# zeta2rework_lw_v32_rework.net
KiCad netlist of a schematic drawn in EAGLE
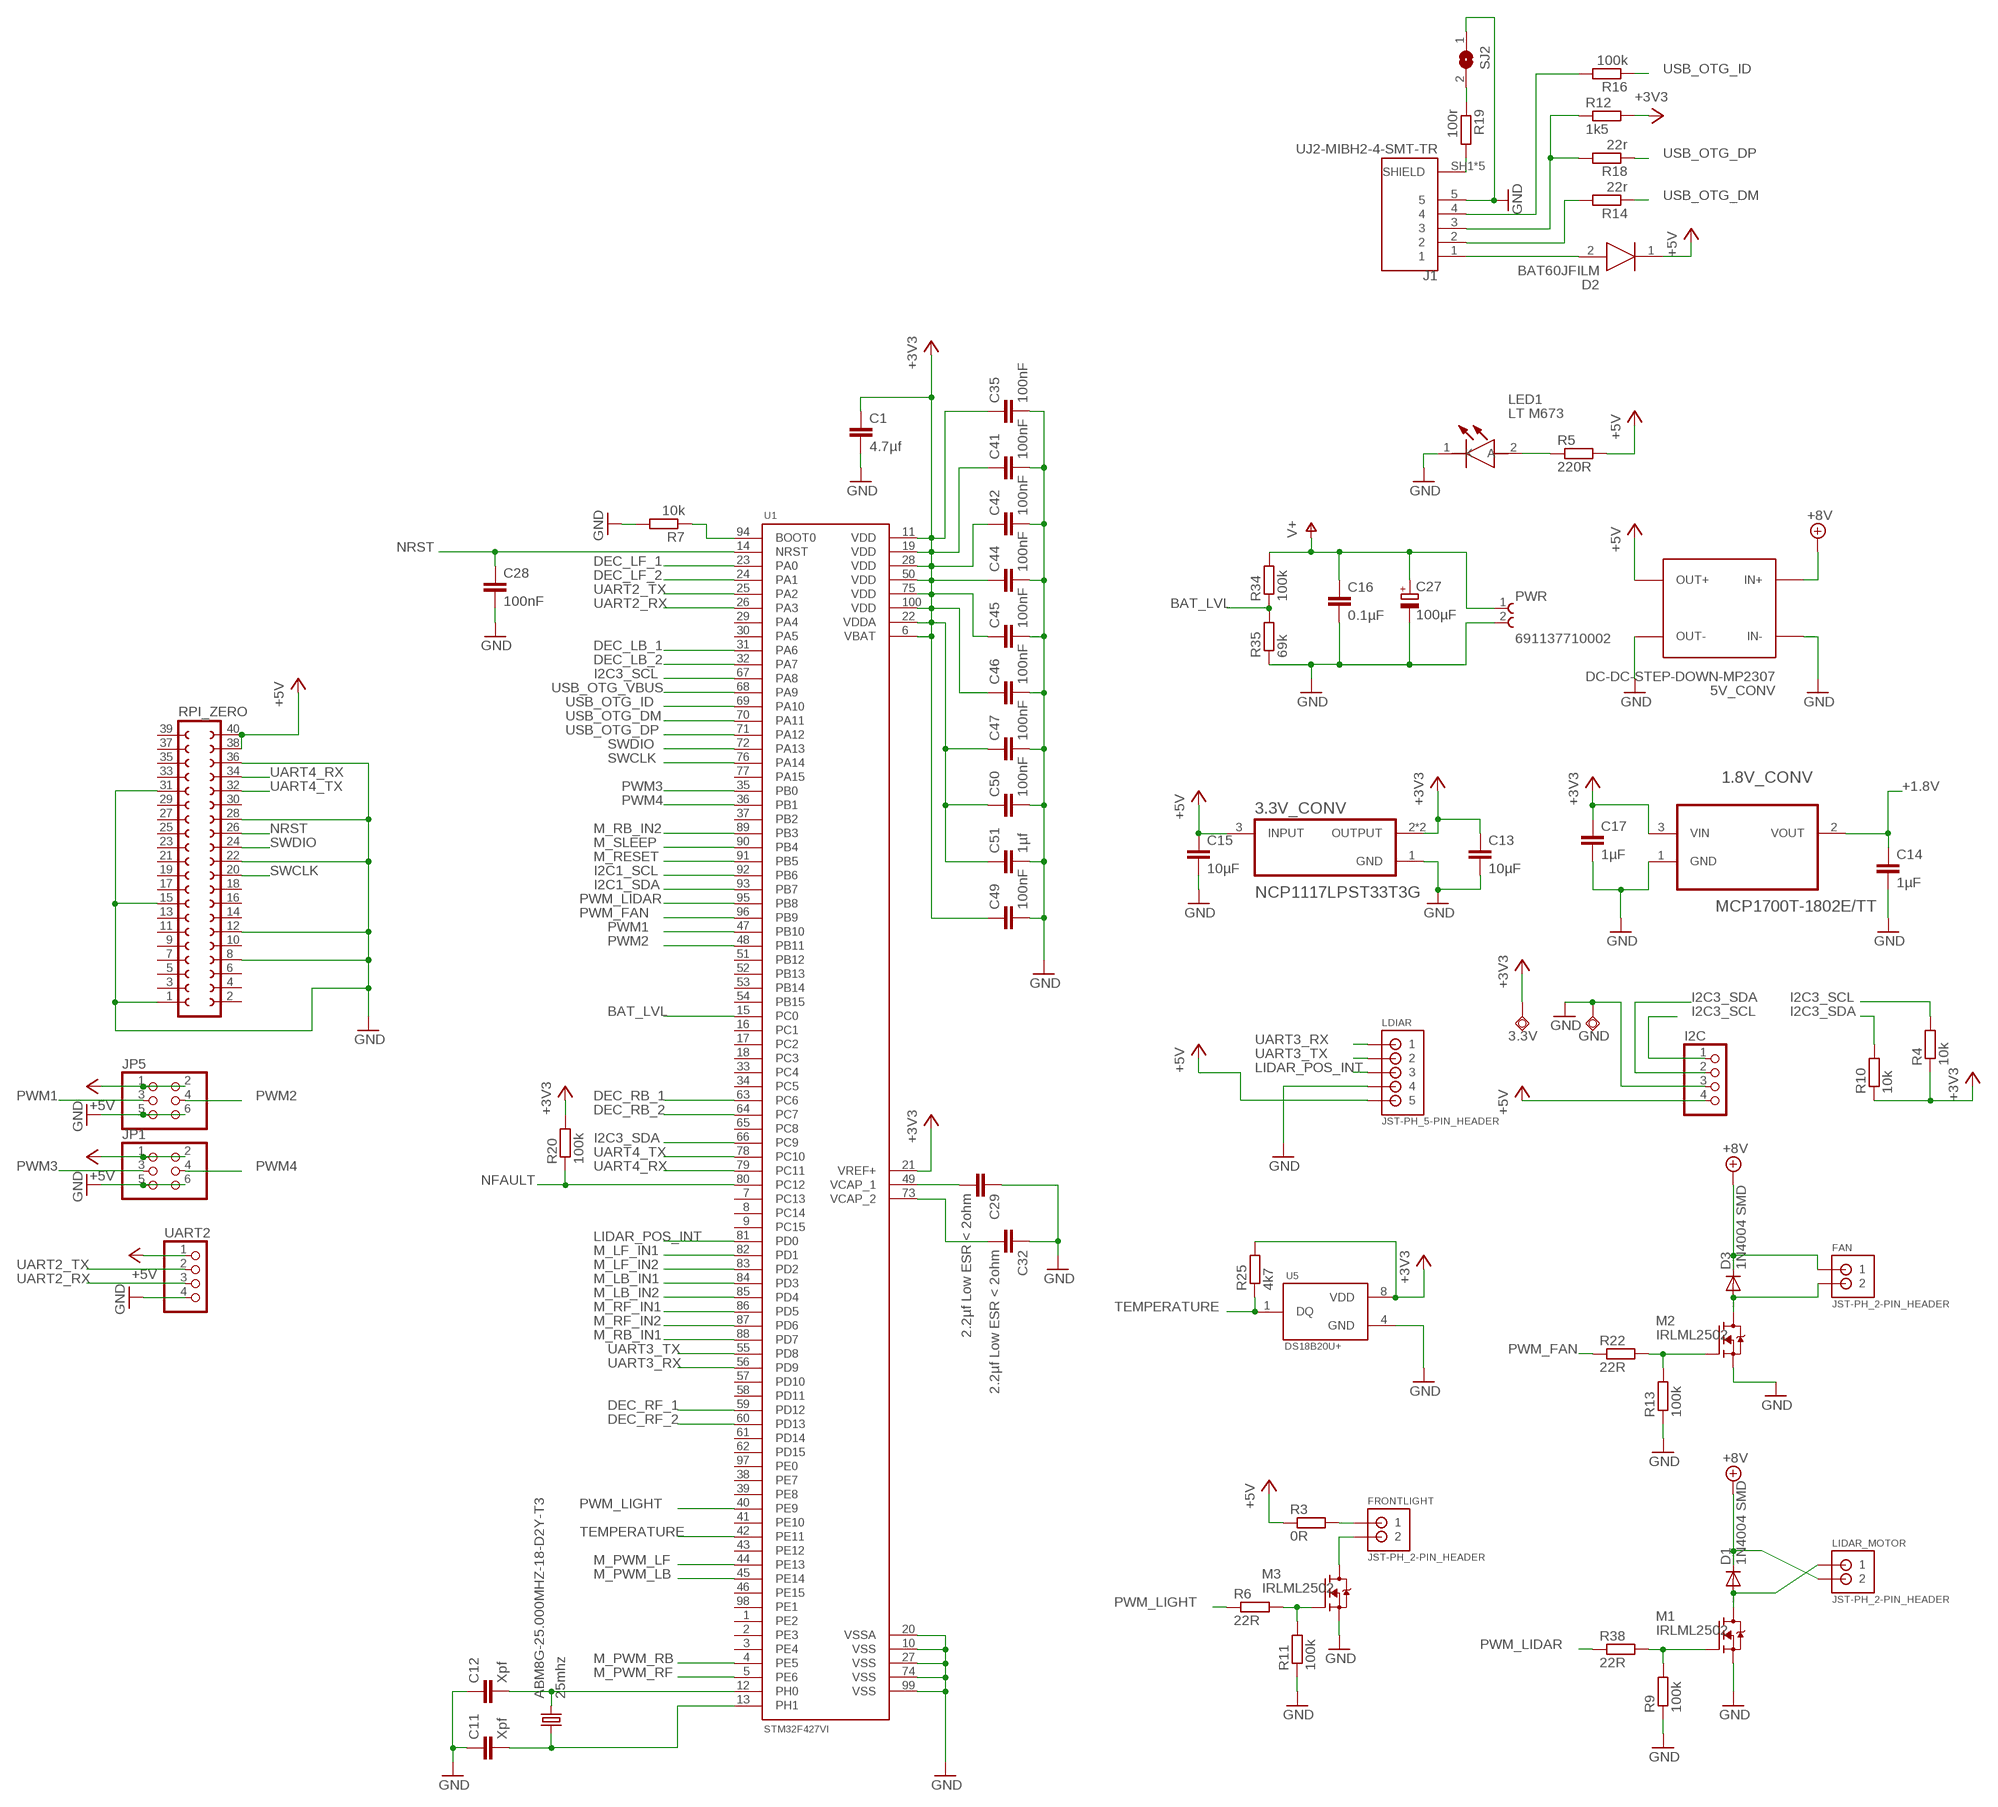
[diagram p0: schematic, sheet 1, part 1 of 2]
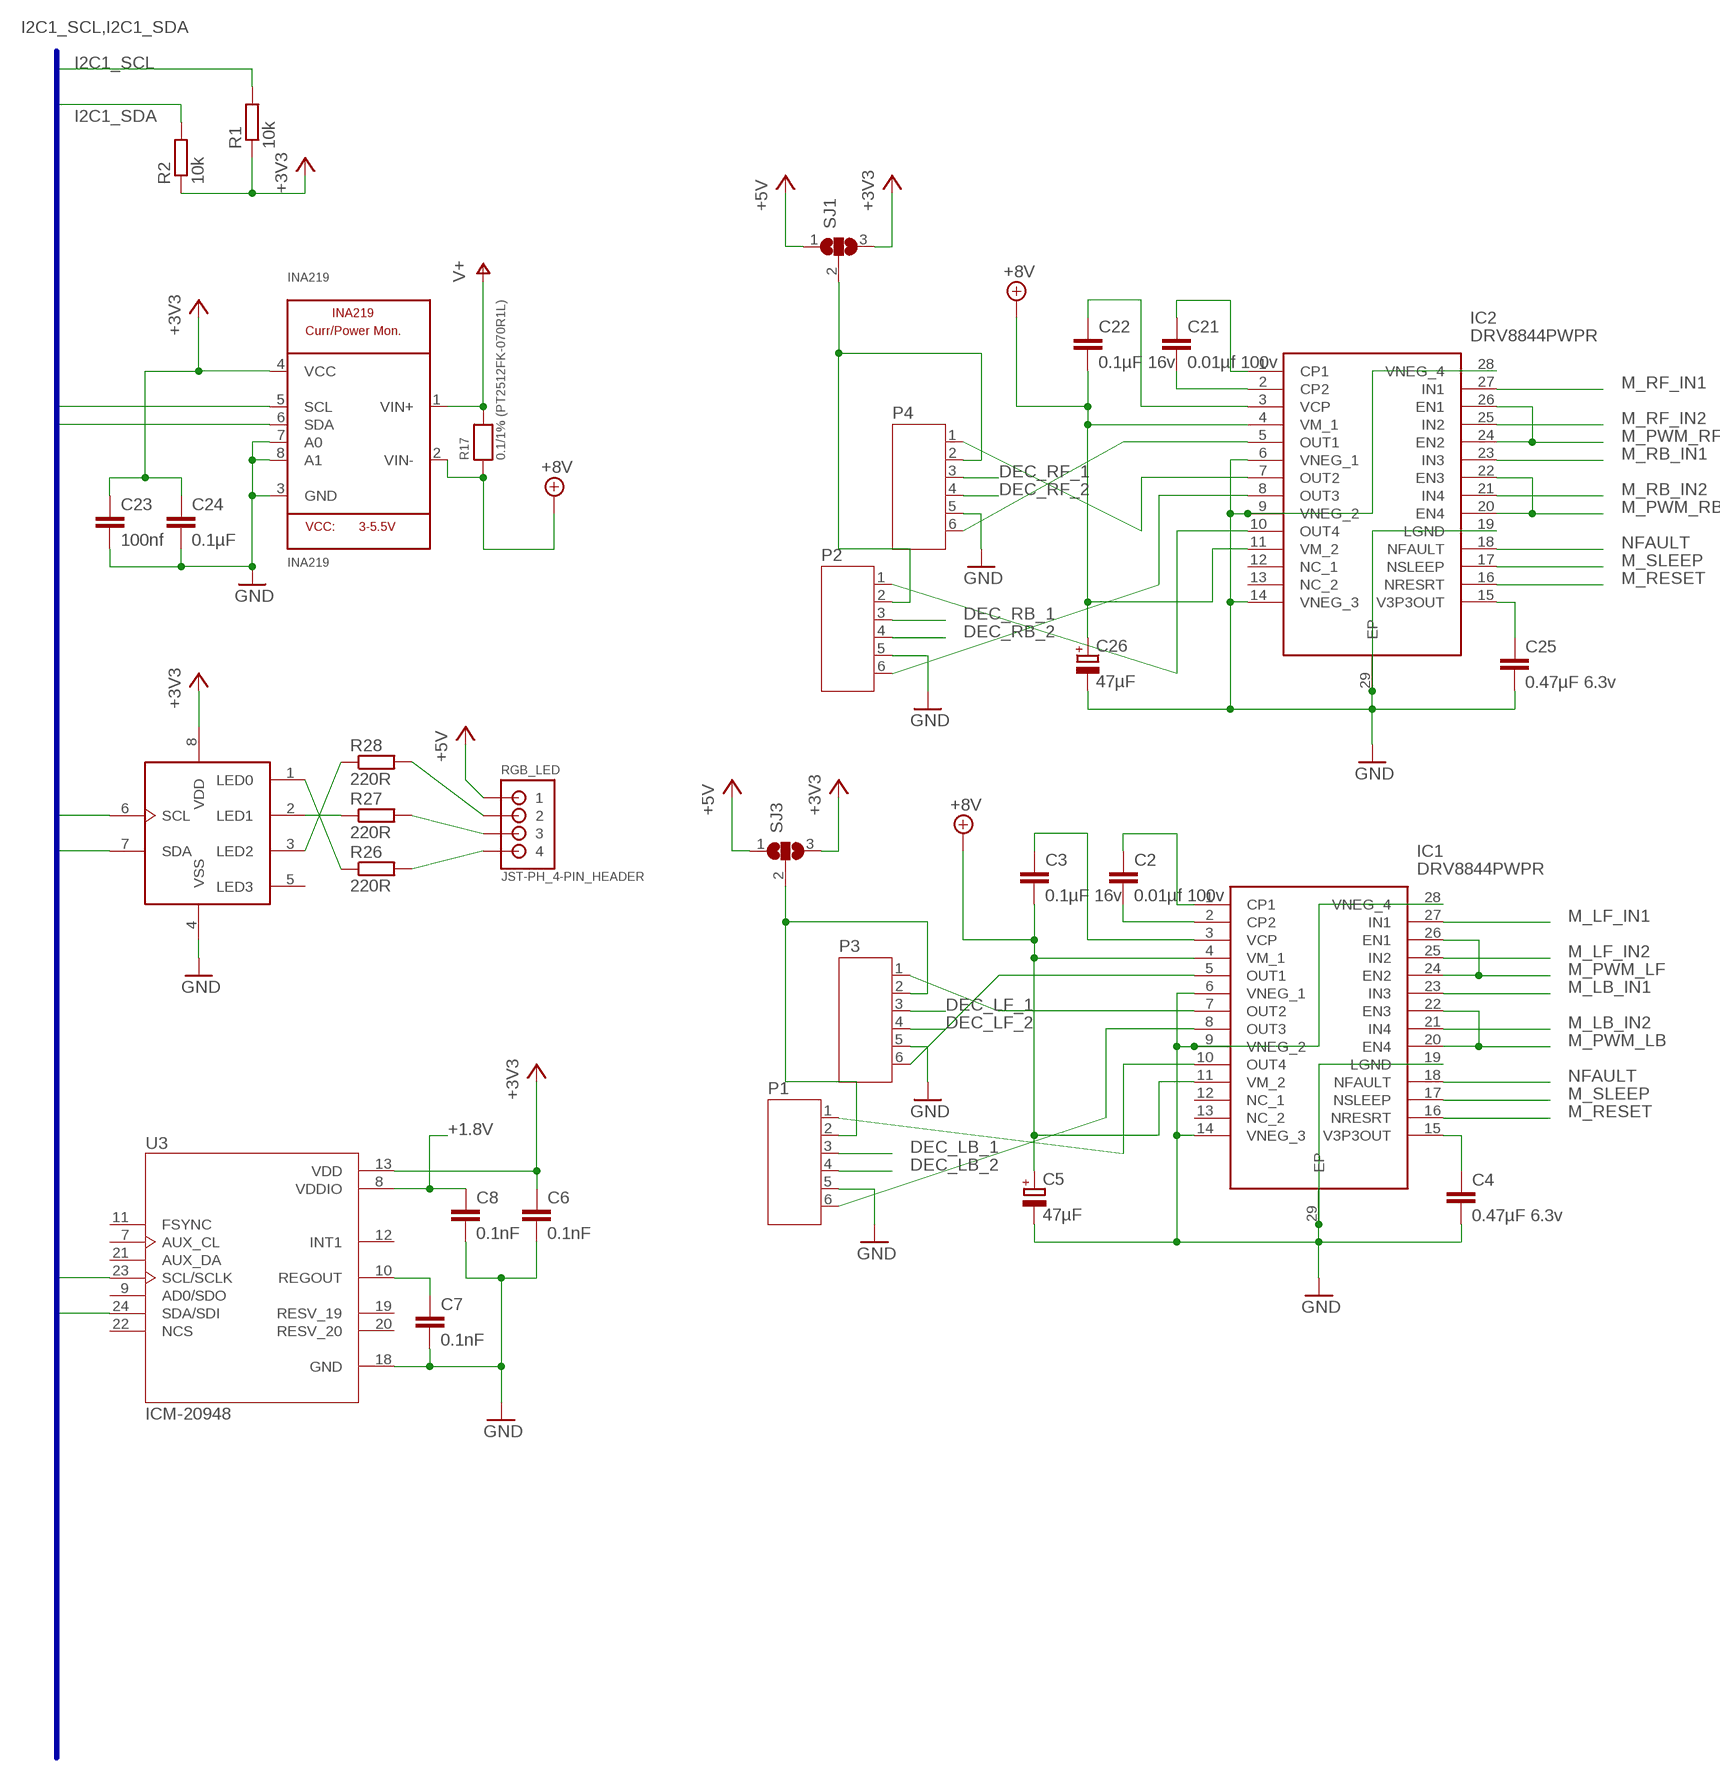
[diagram p1: schematic, sheet 1, part 2 of 2]

(export (version "E")
  (design (tool "Eeschema 10.0.6"))
  (components
    (comp (ref "1.8V_CONV")
      (value "MCP1700T-1802E/TT")
      (footprint "eagle-import:SOT95P237X112-3N")
      (fields (field (name "MF") "Microchip") (field (name "MP") "MCP1700T-2102E/TT"))
      (libsource (lib "eagle-import") (part "MCP1700T-2102E/TT"))
    )
    (comp (ref "3.3V")
      (value "TPSQTP20R")
      (footprint "eagle-import:TP20R")
      (libsource (lib "eagle-import") (part "TPSQTP20R"))
    )
    (comp (ref "3.3V_CONV")
      (value "NCP1117LPST33T3G")
      (footprint "eagle-import:SOT230P700X175-4N")
      (fields (field (name "MF") "ON Semiconductor"))
      (libsource (lib "eagle-import") (part "NCP1117LPST33T3G"))
    )
    (comp (ref "5V_CONV")
      (value "DC-DC-STEP-DOWN-MP2307")
      (footprint "eagle-import:DC-DC-STEP-DOWN-MP2307")
      (libsource (lib "eagle-import") (part "DC-DC-STEP-DOWN-MP2307"))
    )
    (comp (ref "ABM8G-25.000MHZ-18-D2Y-T3")
      (value "25mhz")
      (footprint "eagle-import:5.0X3.2_KX-9A")
      (libsource (lib "eagle-import") (part "KX-9A"))
    )
    (comp (ref "C1")
      (value "4.7µf")
      (footprint "eagle-import:C0603")
      (libsource (lib "eagle-import") (part "C-EUC0603"))
    )
    (comp (ref "C2")
      (value "0.01µf 100v")
      (footprint "eagle-import:C0603")
      (libsource (lib "eagle-import") (part "C-EUC0603"))
    )
    (comp (ref "C3")
      (value "0.1µF 16v")
      (footprint "eagle-import:C0603")
      (libsource (lib "eagle-import") (part "C-EUC0603"))
    )
    (comp (ref "C4")
      (value "0.47µF 6.3v")
      (footprint "eagle-import:C0603")
      (libsource (lib "eagle-import") (part "C-EUC0603"))
    )
    (comp (ref "C5")
      (value "47µF")
      (footprint "eagle-import:UD-5X5,8_NICHICON")
      (libsource (lib "eagle-import") (part "CPOL-EUUD-5X5,8"))
    )
    (comp (ref "C6")
      (value "0.1nF")
      (footprint "eagle-import:C0603")
      (libsource (lib "eagle-import") (part "C-EUC0603"))
    )
    (comp (ref "C7")
      (value "0.1nF")
      (footprint "eagle-import:C0603")
      (libsource (lib "eagle-import") (part "C-EUC0603"))
    )
    (comp (ref "C8")
      (value "0.1nF")
      (footprint "eagle-import:C0603")
      (libsource (lib "eagle-import") (part "C-EUC0603"))
    )
    (comp (ref "C11")
      (value "Xpf")
      (footprint "eagle-import:C0603")
      (libsource (lib "eagle-import") (part "C-EUC0603"))
    )
    (comp (ref "C12")
      (value "Xpf")
      (footprint "eagle-import:C0603")
      (libsource (lib "eagle-import") (part "C-EUC0603"))
    )
    (comp (ref "C13")
      (value "10µF")
      (footprint "eagle-import:C1206")
      (libsource (lib "eagle-import") (part "C-EUC1206"))
    )
    (comp (ref "C14")
      (value "1µF")
      (footprint "eagle-import:C0603")
      (libsource (lib "eagle-import") (part "C-EUC0603"))
    )
    (comp (ref "C15")
      (value "10µF")
      (footprint "eagle-import:C1206")
      (libsource (lib "eagle-import") (part "C-EUC1206"))
    )
    (comp (ref "C16")
      (value "0.1µF")
      (footprint "eagle-import:C0603")
      (libsource (lib "eagle-import") (part "C-EUC0603"))
    )
    (comp (ref "C17")
      (value "1µF")
      (footprint "eagle-import:C0603")
      (libsource (lib "eagle-import") (part "C-EUC0603"))
    )
    (comp (ref "C21")
      (value "0.01µf 100v")
      (footprint "eagle-import:C0603")
      (libsource (lib "eagle-import") (part "C-EUC0603"))
    )
    (comp (ref "C22")
      (value "0.1µF 16v")
      (footprint "eagle-import:C0603")
      (libsource (lib "eagle-import") (part "C-EUC0603"))
    )
    (comp (ref "C23")
      (value "100nf")
      (footprint "eagle-import:C0603")
      (libsource (lib "eagle-import") (part "C-EUC0603"))
    )
    (comp (ref "C24")
      (value "0.1µF")
      (footprint "eagle-import:C0603")
      (libsource (lib "eagle-import") (part "C-EUC0603"))
    )
    (comp (ref "C25")
      (value "0.47µF 6.3v")
      (footprint "eagle-import:C0603")
      (libsource (lib "eagle-import") (part "C-EUC0603"))
    )
    (comp (ref "C26")
      (value "47µF")
      (footprint "eagle-import:UD-5X5,8_NICHICON")
      (libsource (lib "eagle-import") (part "CPOL-EUUD-5X5,8"))
    )
    (comp (ref "C27")
      (value "100µF")
      (footprint "eagle-import:UD-5X5,8_NICHICON")
      (libsource (lib "eagle-import") (part "CPOL-EUUD-5X5,8"))
    )
    (comp (ref "C28")
      (value "100nF")
      (footprint "eagle-import:C0603")
      (libsource (lib "eagle-import") (part "C-EUC0603"))
    )
    (comp (ref "C29")
      (value "2.2µf Low ESR < 2ohm")
      (footprint "eagle-import:C1206")
      (libsource (lib "eagle-import") (part "C-EUC1206"))
    )
    (comp (ref "C32")
      (value "2.2µf Low ESR < 2ohm")
      (footprint "eagle-import:C1206")
      (libsource (lib "eagle-import") (part "C-EUC1206"))
    )
    (comp (ref "C35")
      (value "100nF")
      (footprint "eagle-import:C0603")
      (libsource (lib "eagle-import") (part "C-EUC0603"))
    )
    (comp (ref "C41")
      (value "100nF")
      (footprint "eagle-import:C0603")
      (libsource (lib "eagle-import") (part "C-EUC0603"))
    )
    (comp (ref "C42")
      (value "100nF")
      (footprint "eagle-import:C0603")
      (libsource (lib "eagle-import") (part "C-EUC0603"))
    )
    (comp (ref "C44")
      (value "100nF")
      (footprint "eagle-import:C0603")
      (libsource (lib "eagle-import") (part "C-EUC0603"))
    )
    (comp (ref "C45")
      (value "100nF")
      (footprint "eagle-import:C0603")
      (libsource (lib "eagle-import") (part "C-EUC0603"))
    )
    (comp (ref "C46")
      (value "100nF")
      (footprint "eagle-import:C0603")
      (libsource (lib "eagle-import") (part "C-EUC0603"))
    )
    (comp (ref "C47")
      (value "100nF")
      (footprint "eagle-import:C0603")
      (libsource (lib "eagle-import") (part "C-EUC0603"))
    )
    (comp (ref "C49")
      (value "100nF")
      (footprint "eagle-import:C0603")
      (libsource (lib "eagle-import") (part "C-EUC0603"))
    )
    (comp (ref "C50")
      (value "100nF")
      (footprint "eagle-import:C0603")
      (libsource (lib "eagle-import") (part "C-EUC0603"))
    )
    (comp (ref "C51")
      (value "1µf")
      (footprint "eagle-import:C0603")
      (libsource (lib "eagle-import") (part "C-EUC0603"))
    )
    (comp (ref "D1")
      (value "1N4004 SMD")
      (footprint "eagle-import:DO214AC")
      (libsource (lib "eagle-import") (part "DIODE-DO214AC"))
    )
    (comp (ref "D2")
      (value "BAT60JFILM")
      (footprint "eagle-import:SOD2513X117N")
      (fields (field (name "MOUSER_PART_NUMBER") "511-BAT60JFILM") (field (name "RS_PART_NUMBER") "1458781"))
      (libsource (lib "eagle-import") (part "BAT60JFILM"))
    )
    (comp (ref "D3")
      (value "1N4004 SMD")
      (footprint "eagle-import:DO214AC")
      (libsource (lib "eagle-import") (part "DIODE-DO214AC"))
    )
    (comp (ref "FAN")
      (value "JST-PH_2-PIN_HEADER")
      (footprint "eagle-import:JST_B2B-PH_HEADER")
      (libsource (lib "eagle-import") (part "JST-PH_2-PIN_HEADER"))
    )
    (comp (ref "FRONTLIGHT")
      (value "JST-PH_2-PIN_HEADER")
      (footprint "eagle-import:JST_B2B-PH_HEADER")
      (libsource (lib "eagle-import") (part "JST-PH_2-PIN_HEADER"))
    )
    (comp (ref "GND")
      (value "TPSQTP20R")
      (footprint "eagle-import:TP20R")
      (libsource (lib "eagle-import") (part "TPSQTP20R"))
    )
    (comp (ref "I2C")
      (value "PINHD-1X4")
      (footprint "eagle-import:1X04")
      (libsource (lib "eagle-import") (part "PINHD-1X4"))
    )
    (comp (ref "IC1")
      (value "DRV8844PWPR")
      (footprint "eagle-import:SOP65P640X120-29N")
      (fields (field (name "MOUSER_PART_NUMBER") "595-DRV8844PWPR"))
      (libsource (lib "eagle-import") (part "DRV8844PWPR"))
    )
    (comp (ref "IC2")
      (value "DRV8844PWPR")
      (footprint "eagle-import:SOP65P640X120-29N")
      (fields (field (name "MOUSER_PART_NUMBER") "595-DRV8844PWPR"))
      (libsource (lib "eagle-import") (part "DRV8844PWPR"))
    )
    (comp (ref "INA219")
      (value "INA219")
      (footprint "eagle-import:SOT23-8")
      (fields (field (name "MF") "Texas Instruments"))
      (libsource (lib "eagle-import") (part "INA219"))
    )
    (comp (ref "J1")
      (value "UJ2-MIBH2-4-SMT-TR")
      (footprint "eagle-import:CUI_UJ2-MIBH2-4-SMT-TR")
      (fields (field (name "MF") "CUI Inc."))
      (libsource (lib "eagle-import") (part "UJ2-MIBH2-4-SMT-TR"))
    )
    (comp (ref "JP1")
      (value "PINHD-2X3")
      (footprint "eagle-import:2X03")
      (libsource (lib "eagle-import") (part "PINHD-2X3"))
    )
    (comp (ref "JP5")
      (value "PINHD-2X3")
      (footprint "eagle-import:2X03")
      (libsource (lib "eagle-import") (part "PINHD-2X3"))
    )
    (comp (ref "LDIAR")
      (value "JST-PH_5-PIN_HEADER")
      (footprint "eagle-import:JST_B5B-PH_HEADER")
      (libsource (lib "eagle-import") (part "JST-PH_5-PIN_HEADER"))
    )
    (comp (ref "LED1")
      (value "LT M673")
      (footprint "eagle-import:LTM673-N1R2-25")
      (fields
        (field (name "MANUFACTURER_PART_NUMBER") "LT M673-N1R2-25")
        (field (name "MOUSER_PART_NUMBER") "720-LTM673N1R225Z")
        (field (name "RS_PART_NUMBER") "9133231")
      )
      (libsource (lib "eagle-import") (part "LT_M673-N1R2-25"))
    )
    (comp (ref "LIDAR_MOTOR")
      (value "JST-PH_2-PIN_HEADER")
      (footprint "eagle-import:JST_B2B-PH_HEADER")
      (libsource (lib "eagle-import") (part "JST-PH_2-PIN_HEADER"))
    )
    (comp (ref "M1")
      (value "IRLML2502")
      (footprint "eagle-import:SOT23")
      (fields (field (name "MF") "Infineon") (field (name "MP") "IRLML2502TRPBF"))
      (libsource (lib "eagle-import") (part "IRLML2502TRPBF"))
    )
    (comp (ref "M2")
      (value "IRLML2502")
      (footprint "eagle-import:SOT23")
      (fields (field (name "MF") "Infineon") (field (name "MP") "IRLML2502TRPBF"))
      (libsource (lib "eagle-import") (part "IRLML2502TRPBF"))
    )
    (comp (ref "M3")
      (value "IRLML2502")
      (footprint "eagle-import:SOT23")
      (fields (field (name "MF") "Infineon") (field (name "MP") "IRLML2502TRPBF"))
      (libsource (lib "eagle-import") (part "IRLML2502TRPBF"))
    )
    (comp (ref "P1")
      (value "JST-PH6")
      (footprint "eagle-import:JST-PH6")
      (libsource (lib "eagle-import") (part "JST-PH6"))
    )
    (comp (ref "P2")
      (value "JST-PH6")
      (footprint "eagle-import:JST-PH6")
      (libsource (lib "eagle-import") (part "JST-PH6"))
    )
    (comp (ref "P3")
      (value "JST-PH6")
      (footprint "eagle-import:JST-PH6")
      (libsource (lib "eagle-import") (part "JST-PH6"))
    )
    (comp (ref "P4")
      (value "JST-PH6")
      (footprint "eagle-import:JST-PH6")
      (libsource (lib "eagle-import") (part "JST-PH6"))
    )
    (comp (ref "PCA9533")
      (value "PCA9533")
      (footprint "eagle-import:SOIC8")
      (libsource (lib "eagle-import") (part "PCA9533"))
    )
    (comp (ref "PWR")
      (value "691137710002")
      (footprint "eagle-import:691137710002")
      (fields (field (name "MF") "Wurth Electronics"))
      (libsource (lib "eagle-import") (part "691137710002"))
    )
    (comp (ref "R1")
      (value "10k")
      (footprint "eagle-import:R0603")
      (libsource (lib "eagle-import") (part "R-EU_R0603"))
    )
    (comp (ref "R2")
      (value "10k")
      (footprint "eagle-import:R0603")
      (libsource (lib "eagle-import") (part "R-EU_R0603"))
    )
    (comp (ref "R3")
      (value "0R")
      (footprint "eagle-import:R0603")
      (libsource (lib "eagle-import") (part "R-EU_R0603"))
    )
    (comp (ref "R4")
      (value "10k")
      (footprint "eagle-import:R0603")
      (libsource (lib "eagle-import") (part "R-EU_R0603"))
    )
    (comp (ref "R5")
      (value "220R")
      (footprint "eagle-import:R0603")
      (libsource (lib "eagle-import") (part "R-EU_R0603"))
    )
    (comp (ref "R6")
      (value "22R")
      (footprint "eagle-import:R0603")
      (libsource (lib "eagle-import") (part "R-EU_R0603"))
    )
    (comp (ref "R7")
      (value "10k")
      (footprint "eagle-import:R0603")
      (libsource (lib "eagle-import") (part "R-EU_R0603"))
    )
    (comp (ref "R9")
      (value "100k")
      (footprint "eagle-import:R0603")
      (libsource (lib "eagle-import") (part "R-EU_R0603"))
    )
    (comp (ref "R10")
      (value "10k")
      (footprint "eagle-import:R0603")
      (libsource (lib "eagle-import") (part "R-EU_R0603"))
    )
    (comp (ref "R11")
      (value "100k")
      (footprint "eagle-import:R0603")
      (libsource (lib "eagle-import") (part "R-EU_R0603"))
    )
    (comp (ref "R12")
      (value "1k5")
      (footprint "eagle-import:R0603")
      (libsource (lib "eagle-import") (part "R-EU_R0603"))
    )
    (comp (ref "R13")
      (value "100k")
      (footprint "eagle-import:R0603")
      (libsource (lib "eagle-import") (part "R-EU_R0603"))
    )
    (comp (ref "R14")
      (value "22r")
      (footprint "eagle-import:R0603")
      (libsource (lib "eagle-import") (part "R-EU_R0603"))
    )
    (comp (ref "R16")
      (value "100k")
      (footprint "eagle-import:R0603")
      (libsource (lib "eagle-import") (part "R-EU_R0603"))
    )
    (comp (ref "R17")
      (value "0.1/1% (PT2512FK-070R1L)")
      (footprint "eagle-import:2512")
      (libsource (lib "eagle-import") (part "RESISTOR2512"))
    )
    (comp (ref "R18")
      (value "22r")
      (footprint "eagle-import:R0603")
      (libsource (lib "eagle-import") (part "R-EU_R0603"))
    )
    (comp (ref "R19")
      (value "100r")
      (footprint "eagle-import:R0603")
      (libsource (lib "eagle-import") (part "R-EU_R0603"))
    )
    (comp (ref "R20")
      (value "100k")
      (footprint "eagle-import:R0603")
      (libsource (lib "eagle-import") (part "R-EU_R0603"))
    )
    (comp (ref "R22")
      (value "22R")
      (footprint "eagle-import:R0603")
      (libsource (lib "eagle-import") (part "R-EU_R0603"))
    )
    (comp (ref "R25")
      (value "4k7")
      (footprint "eagle-import:R0603")
      (libsource (lib "eagle-import") (part "R-EU_R0603"))
    )
    (comp (ref "R26")
      (value "220R")
      (footprint "eagle-import:R0603")
      (libsource (lib "eagle-import") (part "R-EU_R0603"))
    )
    (comp (ref "R27")
      (value "220R")
      (footprint "eagle-import:R0603")
      (libsource (lib "eagle-import") (part "R-EU_R0603"))
    )
    (comp (ref "R28")
      (value "220R")
      (footprint "eagle-import:R0603")
      (libsource (lib "eagle-import") (part "R-EU_R0603"))
    )
    (comp (ref "R34")
      (value "100k")
      (footprint "eagle-import:R0603")
      (libsource (lib "eagle-import") (part "R-EU_R0603"))
    )
    (comp (ref "R35")
      (value "69k")
      (footprint "eagle-import:R0603")
      (libsource (lib "eagle-import") (part "R-EU_R0603"))
    )
    (comp (ref "R38")
      (value "22R")
      (footprint "eagle-import:R0603")
      (libsource (lib "eagle-import") (part "R-EU_R0603"))
    )
    (comp (ref "RGB_LED")
      (value "JST-PH_4-PIN_HEADER")
      (footprint "eagle-import:JST_B4B-PH_HEADER")
      (libsource (lib "eagle-import") (part "JST-PH_4-PIN_HEADER"))
    )
    (comp (ref "RPI_ZERO")
      (value "FE20-2")
      (footprint "eagle-import:FE20-2")
      (libsource (lib "eagle-import") (part "FE20-2"))
    )
    (comp (ref "SJ1")
      (value "SJ2W")
      (footprint "eagle-import:SJ_2")
      (libsource (lib "eagle-import") (part "SJ2W"))
    )
    (comp (ref "SJ2") (value "SJ") (footprint "eagle-import:SJ") (libsource (lib "eagle-import") (part "SJ")))
    (comp (ref "SJ3")
      (value "SJ2W")
      (footprint "eagle-import:SJ_2")
      (libsource (lib "eagle-import") (part "SJ2W"))
    )
    (comp (ref "U1")
      (value "STM32F427VI")
      (footprint "eagle-import:QFP50P1600X1600X160-100N")
      (fields (field (name "MF") "STMicroelectronics") (field (name "MP") "STM32F427VGT7"))
      (libsource (lib "eagle-import") (part "STM32F427VGT7"))
    )
    (comp (ref "U3")
      (value "ICM-20948")
      (footprint "eagle-import:QFN40P300X300X105-25N")
      (fields (field (name "MF") "TDK InvenSense"))
      (libsource (lib "eagle-import") (part "ICM-20948"))
    )
    (comp (ref "U5")
      (value "DS18B20U+")
      (footprint "eagle-import:SOP65P490X95-8N")
      (fields (field (name "MF") "Maxim"))
      (libsource (lib "eagle-import") (part "DS18B20U+"))
    )
    (comp (ref "UART2")
      (value "PINHD-1X4")
      (footprint "eagle-import:1X04")
      (libsource (lib "eagle-import") (part "PINHD-1X4"))
    )
  )
  (nets
    (net (code "1") (name "+3V3") (class "Default")
      (node (ref "1.8V_CONV") (pin "3") (pinfunction "VIN_3") (pintype "input"))
      (node (ref "3.3V") (pin "TP") (pinfunction "TP_TP") (pintype "input"))
      (node (ref "3.3V_CONV") (pin "2") (pinfunction "OUTPUT_2") (pintype "output"))
      (node (ref "3.3V_CONV") (pin "4") (pinfunction "OUTPUT_4") (pintype "output"))
      (node (ref "C1") (pin "1") (pinfunction "1_1") (pintype "passive"))
      (node (ref "C13") (pin "1") (pinfunction "1_1") (pintype "passive"))
      (node (ref "C17") (pin "1") (pinfunction "1_1") (pintype "passive"))
      (node (ref "C23") (pin "1") (pinfunction "1_1") (pintype "passive"))
      (node (ref "C24") (pin "1") (pinfunction "1_1") (pintype "passive"))
      (node (ref "C35") (pin "1") (pinfunction "1_1") (pintype "passive"))
      (node (ref "C41") (pin "1") (pinfunction "1_1") (pintype "passive"))
      (node (ref "C42") (pin "1") (pinfunction "1_1") (pintype "passive"))
      (node (ref "C44") (pin "1") (pinfunction "1_1") (pintype "passive"))
      (node (ref "C45") (pin "1") (pinfunction "1_1") (pintype "passive"))
      (node (ref "C46") (pin "1") (pinfunction "1_1") (pintype "passive"))
      (node (ref "C47") (pin "1") (pinfunction "1_1") (pintype "passive"))
      (node (ref "C49") (pin "1") (pinfunction "1_1") (pintype "passive"))
      (node (ref "C50") (pin "1") (pinfunction "1_1") (pintype "passive"))
      (node (ref "C51") (pin "1") (pinfunction "1_1") (pintype "passive"))
      (node (ref "C6") (pin "1") (pinfunction "1_1") (pintype "passive"))
      (node (ref "INA219") (pin "4") (pinfunction "VCC_4") (pintype "bidirectional"))
      (node (ref "PCA9533") (pin "8") (pinfunction "VDD_8") (pintype "power_in"))
      (node (ref "R1") (pin "1") (pinfunction "1_1") (pintype "passive"))
      (node (ref "R10") (pin "1") (pinfunction "1_1") (pintype "passive"))
      (node (ref "R12") (pin "2") (pinfunction "2_2") (pintype "passive"))
      (node (ref "R2") (pin "1") (pinfunction "1_1") (pintype "passive"))
      (node (ref "R20") (pin "2") (pinfunction "2_2") (pintype "passive"))
      (node (ref "R25") (pin "2") (pinfunction "2_2") (pintype "passive"))
      (node (ref "R4") (pin "1") (pinfunction "1_1") (pintype "passive"))
      (node (ref "SJ1") (pin "3") (pinfunction "3_3") (pintype "passive"))
      (node (ref "SJ3") (pin "3") (pinfunction "3_3") (pintype "passive"))
      (node (ref "U1") (pin "100") (pinfunction "VDD_100") (pintype "power_in"))
      (node (ref "U1") (pin "11") (pinfunction "VDD_11") (pintype "power_in"))
      (node (ref "U1") (pin "19") (pinfunction "VDD_19") (pintype "power_in"))
      (node (ref "U1") (pin "21") (pinfunction "VREF+_21") (pintype "power_in"))
      (node (ref "U1") (pin "22") (pinfunction "VDDA_22") (pintype "power_in"))
      (node (ref "U1") (pin "28") (pinfunction "VDD_28") (pintype "power_in"))
      (node (ref "U1") (pin "50") (pinfunction "VDD_50") (pintype "power_in"))
      (node (ref "U1") (pin "6") (pinfunction "VBAT_6") (pintype "power_in"))
      (node (ref "U1") (pin "75") (pinfunction "VDD_75") (pintype "power_in"))
      (node (ref "U3") (pin "13") (pinfunction "VDD_13") (pintype "power_in"))
      (node (ref "U5") (pin "8") (pinfunction "VDD_8") (pintype "power_in"))
    )
    (net (code "2") (name "+5V") (class "Default")
      (node (ref "3.3V_CONV") (pin "3") (pinfunction "INPUT_3") (pintype "input"))
      (node (ref "5V_CONV") (pin "OUT+") (pinfunction "OUT+_OUT+") (pintype "bidirectional"))
      (node (ref "C15") (pin "1") (pinfunction "1_1") (pintype "passive"))
      (node (ref "D2") (pin "1") (pinfunction "K_1") (pintype "bidirectional"))
      (node (ref "I2C") (pin "4") (pinfunction "4_4") (pintype "passive"))
      (node (ref "JP1") (pin "1") (pinfunction "1_1") (pintype "passive"))
      (node (ref "JP1") (pin "2") (pinfunction "2_2") (pintype "passive"))
      (node (ref "JP5") (pin "1") (pinfunction "1_1") (pintype "passive"))
      (node (ref "JP5") (pin "2") (pinfunction "2_2") (pintype "passive"))
      (node (ref "LDIAR") (pin "P5") (pinfunction "5_P5") (pintype "bidirectional"))
      (node (ref "R3") (pin "1") (pinfunction "1_1") (pintype "passive"))
      (node (ref "R5") (pin "2") (pinfunction "2_2") (pintype "passive"))
      (node (ref "RGB_LED") (pin "P1") (pinfunction "1_P1") (pintype "bidirectional"))
      (node (ref "RPI_ZERO") (pin "38") (pinfunction "38_38") (pintype "passive"))
      (node (ref "RPI_ZERO") (pin "40") (pinfunction "40_40") (pintype "passive"))
      (node (ref "SJ1") (pin "1") (pinfunction "1_1") (pintype "passive"))
      (node (ref "SJ3") (pin "1") (pinfunction "1_1") (pintype "passive"))
      (node (ref "UART2") (pin "1") (pinfunction "1_1") (pintype "passive"))
    )
    (net (code "3") (name "+8V") (class "Default")
      (node (ref "5V_CONV") (pin "IN+") (pinfunction "IN+_IN+") (pintype "bidirectional"))
      (node (ref "C22") (pin "2") (pinfunction "2_2") (pintype "passive"))
      (node (ref "C26") (pin "+") (pinfunction "+_+") (pintype "passive"))
      (node (ref "C3") (pin "2") (pinfunction "2_2") (pintype "passive"))
      (node (ref "C5") (pin "+") (pinfunction "+_+") (pintype "passive"))
      (node (ref "D1") (pin "C") (pinfunction "C_C") (pintype "passive"))
      (node (ref "D3") (pin "C") (pinfunction "C_C") (pintype "passive"))
      (node (ref "FAN") (pin "P1") (pinfunction "1_P1") (pintype "bidirectional"))
      (node (ref "IC1") (pin "11") (pinfunction "VM_2_11") (pintype "bidirectional"))
      (node (ref "IC1") (pin "4") (pinfunction "VM_1_4") (pintype "bidirectional"))
      (node (ref "IC2") (pin "11") (pinfunction "VM_2_11") (pintype "bidirectional"))
      (node (ref "IC2") (pin "4") (pinfunction "VM_1_4") (pintype "bidirectional"))
      (node (ref "INA219") (pin "2") (pinfunction "VIN-_2") (pintype "bidirectional"))
      (node (ref "LIDAR_MOTOR") (pin "P2") (pinfunction "2_P2") (pintype "bidirectional"))
      (node (ref "R17") (pin "1") (pinfunction "1_1") (pintype "passive"))
    )
    (net (code "4") (name "/+1.8V") (class "Default")
      (node (ref "1.8V_CONV") (pin "2") (pinfunction "VOUT_2") (pintype "output"))
      (node (ref "C14") (pin "1") (pinfunction "1_1") (pintype "passive"))
      (node (ref "C8") (pin "1") (pinfunction "1_1") (pintype "passive"))
      (node (ref "U3") (pin "8") (pinfunction "VDDIO_8") (pintype "power_in"))
    )
    (net (code "5") (name "/BAT_LVL") (class "Default")
      (node (ref "R34") (pin "1") (pinfunction "1_1") (pintype "passive"))
      (node (ref "R35") (pin "2") (pinfunction "2_2") (pintype "passive"))
      (node (ref "U1") (pin "15") (pinfunction "PC0_15") (pintype "bidirectional"))
    )
    (net (code "6") (name "/DEC_LB_1") (class "Default")
      (node (ref "P1") (pin "3") (pinfunction "3_3") (pintype "passive"))
      (node (ref "U1") (pin "31") (pinfunction "PA6_31") (pintype "bidirectional"))
    )
    (net (code "7") (name "/DEC_LB_2") (class "Default")
      (node (ref "P1") (pin "4") (pinfunction "4_4") (pintype "passive"))
      (node (ref "U1") (pin "32") (pinfunction "PA7_32") (pintype "bidirectional"))
    )
    (net (code "8") (name "/DEC_LF_1") (class "Default")
      (node (ref "P3") (pin "3") (pinfunction "3_3") (pintype "passive"))
      (node (ref "U1") (pin "23") (pinfunction "PA0_23") (pintype "bidirectional"))
    )
    (net (code "9") (name "/DEC_LF_2") (class "Default")
      (node (ref "P3") (pin "4") (pinfunction "4_4") (pintype "passive"))
      (node (ref "U1") (pin "24") (pinfunction "PA1_24") (pintype "bidirectional"))
    )
    (net (code "10") (name "/DEC_RB_1") (class "Default")
      (node (ref "P2") (pin "3") (pinfunction "3_3") (pintype "passive"))
      (node (ref "U1") (pin "63") (pinfunction "PC6_63") (pintype "bidirectional"))
    )
    (net (code "11") (name "/DEC_RB_2") (class "Default")
      (node (ref "P2") (pin "4") (pinfunction "4_4") (pintype "passive"))
      (node (ref "U1") (pin "64") (pinfunction "PC7_64") (pintype "bidirectional"))
    )
    (net (code "12") (name "/DEC_RF_1") (class "Default")
      (node (ref "P4") (pin "3") (pinfunction "3_3") (pintype "passive"))
      (node (ref "U1") (pin "59") (pinfunction "PD12_59") (pintype "bidirectional"))
    )
    (net (code "13") (name "/DEC_RF_2") (class "Default")
      (node (ref "P4") (pin "4") (pinfunction "4_4") (pintype "passive"))
      (node (ref "U1") (pin "60") (pinfunction "PD13_60") (pintype "bidirectional"))
    )
    (net (code "14") (name "/I2C1_SCL") (class "Default")
      (node (ref "INA219") (pin "5") (pinfunction "SCL_5") (pintype "bidirectional"))
      (node (ref "PCA9533") (pin "6") (pinfunction "SCL_6") (pintype "input"))
      (node (ref "R1") (pin "2") (pinfunction "2_2") (pintype "passive"))
      (node (ref "U1") (pin "92") (pinfunction "PB6_92") (pintype "bidirectional"))
      (node (ref "U3") (pin "23") (pinfunction "SCL/SCLK_23") (pintype "input"))
    )
    (net (code "15") (name "/I2C1_SDA") (class "Default")
      (node (ref "INA219") (pin "6") (pinfunction "SDA_6") (pintype "bidirectional"))
      (node (ref "PCA9533") (pin "7") (pinfunction "SDA_7") (pintype "bidirectional"))
      (node (ref "R2") (pin "2") (pinfunction "2_2") (pintype "passive"))
      (node (ref "U1") (pin "93") (pinfunction "PB7_93") (pintype "bidirectional"))
      (node (ref "U3") (pin "24") (pinfunction "SDA/SDI_24") (pintype "bidirectional"))
    )
    (net (code "16") (name "/I2C3_SCL") (class "Default")
      (node (ref "I2C") (pin "1") (pinfunction "1_1") (pintype "passive"))
      (node (ref "R4") (pin "2") (pinfunction "2_2") (pintype "passive"))
      (node (ref "U1") (pin "67") (pinfunction "PA8_67") (pintype "bidirectional"))
    )
    (net (code "17") (name "/I2C3_SDA") (class "Default")
      (node (ref "I2C") (pin "2") (pinfunction "2_2") (pintype "passive"))
      (node (ref "R10") (pin "2") (pinfunction "2_2") (pintype "passive"))
      (node (ref "U1") (pin "66") (pinfunction "PC9_66") (pintype "bidirectional"))
    )
    (net (code "18") (name "/LIDAR_POS_INT") (class "Default")
      (node (ref "LDIAR") (pin "P3") (pinfunction "3_P3") (pintype "bidirectional"))
      (node (ref "U1") (pin "81") (pinfunction "PD0_81") (pintype "bidirectional"))
    )
    (net (code "19") (name "/M_LB_IN1") (class "Default")
      (node (ref "IC1") (pin "23") (pinfunction "IN3_23") (pintype "input"))
      (node (ref "U1") (pin "84") (pinfunction "PD3_84") (pintype "bidirectional"))
    )
    (net (code "20") (name "/M_LB_IN2") (class "Default")
      (node (ref "IC1") (pin "21") (pinfunction "IN4_21") (pintype "input"))
      (node (ref "U1") (pin "85") (pinfunction "PD4_85") (pintype "bidirectional"))
    )
    (net (code "21") (name "/M_LF_IN1") (class "Default")
      (node (ref "IC1") (pin "27") (pinfunction "IN1_27") (pintype "input"))
      (node (ref "U1") (pin "82") (pinfunction "PD1_82") (pintype "bidirectional"))
    )
    (net (code "22") (name "/M_LF_IN2") (class "Default")
      (node (ref "IC1") (pin "25") (pinfunction "IN2_25") (pintype "input"))
      (node (ref "U1") (pin "83") (pinfunction "PD2_83") (pintype "bidirectional"))
    )
    (net (code "23") (name "/M_PWM_LB") (class "Default")
      (node (ref "IC1") (pin "20") (pinfunction "EN4_20") (pintype "bidirectional"))
      (node (ref "IC1") (pin "22") (pinfunction "EN3_22") (pintype "bidirectional"))
      (node (ref "U1") (pin "45") (pinfunction "PE14_45") (pintype "bidirectional"))
    )
    (net (code "24") (name "/M_PWM_LF") (class "Default")
      (node (ref "IC1") (pin "24") (pinfunction "EN2_24") (pintype "bidirectional"))
      (node (ref "IC1") (pin "26") (pinfunction "EN1_26") (pintype "bidirectional"))
      (node (ref "U1") (pin "44") (pinfunction "PE13_44") (pintype "bidirectional"))
    )
    (net (code "25") (name "/M_PWM_RB") (class "Default")
      (node (ref "IC2") (pin "20") (pinfunction "EN4_20") (pintype "bidirectional"))
      (node (ref "IC2") (pin "22") (pinfunction "EN3_22") (pintype "bidirectional"))
      (node (ref "U1") (pin "4") (pinfunction "PE5_4") (pintype "bidirectional"))
    )
    (net (code "26") (name "/M_PWM_RF") (class "Default")
      (node (ref "IC2") (pin "24") (pinfunction "EN2_24") (pintype "bidirectional"))
      (node (ref "IC2") (pin "26") (pinfunction "EN1_26") (pintype "bidirectional"))
      (node (ref "U1") (pin "5") (pinfunction "PE6_5") (pintype "bidirectional"))
    )
    (net (code "27") (name "/M_RB_IN1") (class "Default")
      (node (ref "IC2") (pin "23") (pinfunction "IN3_23") (pintype "input"))
      (node (ref "U1") (pin "88") (pinfunction "PD7_88") (pintype "bidirectional"))
    )
    (net (code "28") (name "/M_RB_IN2") (class "Default")
      (node (ref "IC2") (pin "21") (pinfunction "IN4_21") (pintype "input"))
      (node (ref "U1") (pin "89") (pinfunction "PB3_89") (pintype "bidirectional"))
    )
    (net (code "29") (name "/M_RESET") (class "Default")
      (node (ref "IC1") (pin "16") (pinfunction "NRESRT_16") (pintype "bidirectional"))
      (node (ref "IC2") (pin "16") (pinfunction "NRESRT_16") (pintype "bidirectional"))
      (node (ref "U1") (pin "91") (pinfunction "PB5_91") (pintype "bidirectional"))
    )
    (net (code "30") (name "/M_RF_IN1") (class "Default")
      (node (ref "IC2") (pin "27") (pinfunction "IN1_27") (pintype "input"))
      (node (ref "U1") (pin "86") (pinfunction "PD5_86") (pintype "bidirectional"))
    )
    (net (code "31") (name "/M_RF_IN2") (class "Default")
      (node (ref "IC2") (pin "25") (pinfunction "IN2_25") (pintype "input"))
      (node (ref "U1") (pin "87") (pinfunction "PD6_87") (pintype "bidirectional"))
    )
    (net (code "32") (name "/M_SLEEP") (class "Default")
      (node (ref "IC1") (pin "17") (pinfunction "NSLEEP_17") (pintype "bidirectional"))
      (node (ref "IC2") (pin "17") (pinfunction "NSLEEP_17") (pintype "bidirectional"))
      (node (ref "U1") (pin "90") (pinfunction "PB4_90") (pintype "bidirectional"))
    )
    (net (code "33") (name "/NFAULT") (class "Default")
      (node (ref "IC1") (pin "18") (pinfunction "NFAULT_18") (pintype "bidirectional"))
      (node (ref "IC2") (pin "18") (pinfunction "NFAULT_18") (pintype "bidirectional"))
      (node (ref "R20") (pin "1") (pinfunction "1_1") (pintype "passive"))
      (node (ref "U1") (pin "80") (pinfunction "PC12_80") (pintype "bidirectional"))
    )
    (net (code "34") (name "/NRST") (class "Default")
      (node (ref "C28") (pin "1") (pinfunction "1_1") (pintype "passive"))
      (node (ref "RPI_ZERO") (pin "26") (pinfunction "26_26") (pintype "passive"))
      (node (ref "U1") (pin "14") (pinfunction "NRST_14") (pintype "bidirectional"))
    )
    (net (code "35") (name "/PWM1") (class "Default")
      (node (ref "JP5") (pin "3") (pinfunction "3_3") (pintype "passive"))
      (node (ref "U1") (pin "47") (pinfunction "PB10_47") (pintype "bidirectional"))
    )
    (net (code "36") (name "/PWM2") (class "Default")
      (node (ref "JP5") (pin "4") (pinfunction "4_4") (pintype "passive"))
      (node (ref "U1") (pin "48") (pinfunction "PB11_48") (pintype "bidirectional"))
    )
    (net (code "37") (name "/PWM3") (class "Default")
      (node (ref "JP1") (pin "3") (pinfunction "3_3") (pintype "passive"))
      (node (ref "U1") (pin "35") (pinfunction "PB0_35") (pintype "bidirectional"))
    )
    (net (code "38") (name "/PWM4") (class "Default")
      (node (ref "JP1") (pin "4") (pinfunction "4_4") (pintype "passive"))
      (node (ref "U1") (pin "36") (pinfunction "PB1_36") (pintype "bidirectional"))
    )
    (net (code "39") (name "/PWM_FAN") (class "Default")
      (node (ref "R22") (pin "1") (pinfunction "1_1") (pintype "passive"))
      (node (ref "U1") (pin "96") (pinfunction "PB9_96") (pintype "bidirectional"))
    )
    (net (code "40") (name "/PWM_LIDAR") (class "Default")
      (node (ref "R38") (pin "1") (pinfunction "1_1") (pintype "passive"))
      (node (ref "U1") (pin "95") (pinfunction "PB8_95") (pintype "bidirectional"))
    )
    (net (code "41") (name "/PWM_LIGHT") (class "Default")
      (node (ref "R6") (pin "1") (pinfunction "1_1") (pintype "passive"))
      (node (ref "U1") (pin "40") (pinfunction "PE9_40") (pintype "bidirectional"))
    )
    (net (code "42") (name "/SWCLK") (class "Default")
      (node (ref "RPI_ZERO") (pin "20") (pinfunction "20_20") (pintype "passive"))
      (node (ref "U1") (pin "76") (pinfunction "PA14_76") (pintype "bidirectional"))
    )
    (net (code "43") (name "/SWDIO") (class "Default")
      (node (ref "RPI_ZERO") (pin "24") (pinfunction "24_24") (pintype "passive"))
      (node (ref "U1") (pin "72") (pinfunction "PA13_72") (pintype "bidirectional"))
    )
    (net (code "44") (name "/TEMPERATURE") (class "Default")
      (node (ref "R25") (pin "1") (pinfunction "1_1") (pintype "passive"))
      (node (ref "U1") (pin "42") (pinfunction "PE11_42") (pintype "bidirectional"))
      (node (ref "U5") (pin "1") (pinfunction "DQ_1") (pintype "bidirectional"))
    )
    (net (code "45") (name "/UART2_RX") (class "Default")
      (node (ref "U1") (pin "26") (pinfunction "PA3_26") (pintype "bidirectional"))
      (node (ref "UART2") (pin "3") (pinfunction "3_3") (pintype "passive"))
    )
    (net (code "46") (name "/UART2_TX") (class "Default")
      (node (ref "U1") (pin "25") (pinfunction "PA2_25") (pintype "bidirectional"))
      (node (ref "UART2") (pin "2") (pinfunction "2_2") (pintype "passive"))
    )
    (net (code "47") (name "/UART3_RX") (class "Default")
      (node (ref "LDIAR") (pin "P1") (pinfunction "1_P1") (pintype "bidirectional"))
      (node (ref "U1") (pin "56") (pinfunction "PD9_56") (pintype "bidirectional"))
    )
    (net (code "48") (name "/UART3_TX") (class "Default")
      (node (ref "LDIAR") (pin "P2") (pinfunction "2_P2") (pintype "bidirectional"))
      (node (ref "U1") (pin "55") (pinfunction "PD8_55") (pintype "bidirectional"))
    )
    (net (code "49") (name "/UART4_RX") (class "Default")
      (node (ref "RPI_ZERO") (pin "34") (pinfunction "34_34") (pintype "passive"))
      (node (ref "U1") (pin "79") (pinfunction "PC11_79") (pintype "bidirectional"))
    )
    (net (code "50") (name "/UART4_TX") (class "Default")
      (node (ref "RPI_ZERO") (pin "32") (pinfunction "32_32") (pintype "passive"))
      (node (ref "U1") (pin "78") (pinfunction "PC10_78") (pintype "bidirectional"))
    )
    (net (code "51") (name "/USB_OTG_DM") (class "Default")
      (node (ref "R14") (pin "1") (pinfunction "1_1") (pintype "passive"))
      (node (ref "U1") (pin "70") (pinfunction "PA11_70") (pintype "bidirectional"))
    )
    (net (code "52") (name "/USB_OTG_DP") (class "Default")
      (node (ref "R18") (pin "1") (pinfunction "1_1") (pintype "passive"))
      (node (ref "U1") (pin "71") (pinfunction "PA12_71") (pintype "bidirectional"))
    )
    (net (code "53") (name "/USB_OTG_ID") (class "Default")
      (node (ref "R16") (pin "1") (pinfunction "1_1") (pintype "passive"))
      (node (ref "U1") (pin "69") (pinfunction "PA10_69") (pintype "bidirectional"))
    )
    (net (code "54") (name "/USB_OTG_VBUS") (class "Default")
      (node (ref "U1") (pin "68") (pinfunction "PA9_68") (pintype "bidirectional"))
    )
    (net (code "56") (name "GND") (class "Default")
      (node (ref "1.8V_CONV") (pin "1") (pinfunction "GND_1") (pintype "passive"))
      (node (ref "3.3V_CONV") (pin "1") (pinfunction "GND_1") (pintype "power_in"))
      (node (ref "5V_CONV") (pin "IN-") (pinfunction "IN-_IN-") (pintype "bidirectional"))
      (node (ref "5V_CONV") (pin "OUT-") (pinfunction "OUT-_OUT-") (pintype "bidirectional"))
      (node (ref "C1") (pin "2") (pinfunction "2_2") (pintype "passive"))
      (node (ref "C11") (pin "1") (pinfunction "1_1") (pintype "passive"))
      (node (ref "C12") (pin "1") (pinfunction "1_1") (pintype "passive"))
      (node (ref "C13") (pin "2") (pinfunction "2_2") (pintype "passive"))
      (node (ref "C14") (pin "2") (pinfunction "2_2") (pintype "passive"))
      (node (ref "C15") (pin "2") (pinfunction "2_2") (pintype "passive"))
      (node (ref "C16") (pin "2") (pinfunction "2_2") (pintype "passive"))
      (node (ref "C17") (pin "2") (pinfunction "2_2") (pintype "passive"))
      (node (ref "C23") (pin "2") (pinfunction "2_2") (pintype "passive"))
      (node (ref "C24") (pin "2") (pinfunction "2_2") (pintype "passive"))
      (node (ref "C25") (pin "2") (pinfunction "2_2") (pintype "passive"))
      (node (ref "C26") (pin "-") (pinfunction "-_-") (pintype "passive"))
      (node (ref "C27") (pin "-") (pinfunction "-_-") (pintype "passive"))
      (node (ref "C28") (pin "2") (pinfunction "2_2") (pintype "passive"))
      (node (ref "C29") (pin "1") (pinfunction "1_1") (pintype "passive"))
      (node (ref "C32") (pin "1") (pinfunction "1_1") (pintype "passive"))
      (node (ref "C35") (pin "2") (pinfunction "2_2") (pintype "passive"))
      (node (ref "C4") (pin "2") (pinfunction "2_2") (pintype "passive"))
      (node (ref "C41") (pin "2") (pinfunction "2_2") (pintype "passive"))
      (node (ref "C42") (pin "2") (pinfunction "2_2") (pintype "passive"))
      (node (ref "C44") (pin "2") (pinfunction "2_2") (pintype "passive"))
      (node (ref "C45") (pin "2") (pinfunction "2_2") (pintype "passive"))
      (node (ref "C46") (pin "2") (pinfunction "2_2") (pintype "passive"))
      (node (ref "C47") (pin "2") (pinfunction "2_2") (pintype "passive"))
      (node (ref "C49") (pin "2") (pinfunction "2_2") (pintype "passive"))
      (node (ref "C5") (pin "-") (pinfunction "-_-") (pintype "passive"))
      (node (ref "C50") (pin "2") (pinfunction "2_2") (pintype "passive"))
      (node (ref "C51") (pin "2") (pinfunction "2_2") (pintype "passive"))
      (node (ref "C6") (pin "2") (pinfunction "2_2") (pintype "passive"))
      (node (ref "C7") (pin "2") (pinfunction "2_2") (pintype "passive"))
      (node (ref "C8") (pin "2") (pinfunction "2_2") (pintype "passive"))
      (node (ref "GND") (pin "TP") (pinfunction "TP_TP") (pintype "input"))
      (node (ref "I2C") (pin "3") (pinfunction "3_3") (pintype "passive"))
      (node (ref "IC1") (pin "14") (pinfunction "VNEG_3_14") (pintype "bidirectional"))
      (node (ref "IC1") (pin "19") (pinfunction "LGND_19") (pintype "power_in"))
      (node (ref "IC1") (pin "28") (pinfunction "VNEG_4_28") (pintype "bidirectional"))
      (node (ref "IC1") (pin "29") (pinfunction "EP_29") (pintype "power_in"))
      (node (ref "IC1") (pin "6") (pinfunction "VNEG_1_6") (pintype "bidirectional"))
      (node (ref "IC1") (pin "9") (pinfunction "VNEG_2_9") (pintype "bidirectional"))
      (node (ref "IC2") (pin "14") (pinfunction "VNEG_3_14") (pintype "bidirectional"))
      (node (ref "IC2") (pin "19") (pinfunction "LGND_19") (pintype "power_in"))
      (node (ref "IC2") (pin "28") (pinfunction "VNEG_4_28") (pintype "bidirectional"))
      (node (ref "IC2") (pin "29") (pinfunction "EP_29") (pintype "power_in"))
      (node (ref "IC2") (pin "6") (pinfunction "VNEG_1_6") (pintype "bidirectional"))
      (node (ref "IC2") (pin "9") (pinfunction "VNEG_2_9") (pintype "bidirectional"))
      (node (ref "INA219") (pin "3") (pinfunction "GND_3") (pintype "bidirectional"))
      (node (ref "INA219") (pin "7") (pinfunction "A0_7") (pintype "bidirectional"))
      (node (ref "INA219") (pin "8") (pinfunction "A1_8") (pintype "bidirectional"))
      (node (ref "J1") (pin "5") (pinfunction "5_5") (pintype "passive"))
      (node (ref "JP1") (pin "5") (pinfunction "5_5") (pintype "passive"))
      (node (ref "JP1") (pin "6") (pinfunction "6_6") (pintype "passive"))
      (node (ref "JP5") (pin "5") (pinfunction "5_5") (pintype "passive"))
      (node (ref "JP5") (pin "6") (pinfunction "6_6") (pintype "passive"))
      (node (ref "LDIAR") (pin "P4") (pinfunction "4_P4") (pintype "bidirectional"))
      (node (ref "LED1") (pin "1") (pinfunction "K_1") (pintype "bidirectional"))
      (node (ref "M1") (pin "2") (pinfunction "S_2") (pintype "passive"))
      (node (ref "M2") (pin "2") (pinfunction "S_2") (pintype "passive"))
      (node (ref "M3") (pin "2") (pinfunction "S_2") (pintype "passive"))
      (node (ref "P1") (pin "5") (pinfunction "5_5") (pintype "passive"))
      (node (ref "P2") (pin "5") (pinfunction "5_5") (pintype "passive"))
      (node (ref "P3") (pin "5") (pinfunction "5_5") (pintype "passive"))
      (node (ref "P4") (pin "5") (pinfunction "5_5") (pintype "passive"))
      (node (ref "PCA9533") (pin "4") (pinfunction "VSS_4") (pintype "power_in"))
      (node (ref "PWR") (pin "2") (pinfunction "2_2") (pintype "passive"))
      (node (ref "R11") (pin "1") (pinfunction "1_1") (pintype "passive"))
      (node (ref "R13") (pin "1") (pinfunction "1_1") (pintype "passive"))
      (node (ref "R35") (pin "1") (pinfunction "1_1") (pintype "passive"))
      (node (ref "R7") (pin "2") (pinfunction "2_2") (pintype "passive"))
      (node (ref "R9") (pin "1") (pinfunction "1_1") (pintype "passive"))
      (node (ref "RPI_ZERO") (pin "1") (pinfunction "1_1") (pintype "passive"))
      (node (ref "RPI_ZERO") (pin "12") (pinfunction "12_12") (pintype "passive"))
      (node (ref "RPI_ZERO") (pin "15") (pinfunction "15_15") (pintype "passive"))
      (node (ref "RPI_ZERO") (pin "22") (pinfunction "22_22") (pintype "passive"))
      (node (ref "RPI_ZERO") (pin "28") (pinfunction "28_28") (pintype "passive"))
      (node (ref "RPI_ZERO") (pin "31") (pinfunction "31_31") (pintype "passive"))
      (node (ref "RPI_ZERO") (pin "36") (pinfunction "36_36") (pintype "passive"))
      (node (ref "RPI_ZERO") (pin "8") (pinfunction "8_8") (pintype "passive"))
      (node (ref "SJ2") (pin "1") (pinfunction "1_1") (pintype "passive"))
      (node (ref "U1") (pin "10") (pinfunction "VSS_10") (pintype "power_in"))
      (node (ref "U1") (pin "20") (pinfunction "VSSA_20") (pintype "power_in"))
      (node (ref "U1") (pin "27") (pinfunction "VSS_27") (pintype "power_in"))
      (node (ref "U1") (pin "74") (pinfunction "VSS_74") (pintype "power_in"))
      (node (ref "U1") (pin "99") (pinfunction "VSS_99") (pintype "power_in"))
      (node (ref "U3") (pin "18") (pinfunction "GND_18") (pintype "power_in"))
      (node (ref "U5") (pin "4") (pinfunction "GND_4") (pintype "power_in"))
      (node (ref "UART2") (pin "4") (pinfunction "4_4") (pintype "passive"))
    )
    (net (code "57") (name "Net-(ABM8G-25.000MHZ-18-D2Y-T3-2)") (class "Default")
      (node (ref "ABM8G-25.000MHZ-18-D2Y-T3") (pin "3") (pinfunction "2_3") (pintype "passive"))
      (node (ref "C12") (pin "2") (pinfunction "2_2") (pintype "passive"))
      (node (ref "U1") (pin "12") (pinfunction "PH0_12") (pintype "bidirectional"))
    )
    (net (code "58") (name "Net-(D2-A)") (class "Default")
      (node (ref "D2") (pin "2") (pinfunction "A_2") (pintype "bidirectional"))
      (node (ref "J1") (pin "1") (pinfunction "1_1") (pintype "passive"))
    )
    (net (code "59") (name "Net-(FAN-2)") (class "Default")
      (node (ref "D3") (pin "A") (pinfunction "A_A") (pintype "passive"))
      (node (ref "FAN") (pin "P2") (pinfunction "2_P2") (pintype "bidirectional"))
      (node (ref "M2") (pin "3") (pinfunction "D_3") (pintype "passive"))
    )
    (net (code "60") (name "Net-(FRONTLIGHT-1)") (class "Default")
      (node (ref "FRONTLIGHT") (pin "P1") (pinfunction "1_P1") (pintype "bidirectional"))
      (node (ref "R3") (pin "2") (pinfunction "2_2") (pintype "passive"))
    )
    (net (code "61") (name "Net-(FRONTLIGHT-2)") (class "Default")
      (node (ref "FRONTLIGHT") (pin "P2") (pinfunction "2_P2") (pintype "bidirectional"))
      (node (ref "M3") (pin "3") (pinfunction "D_3") (pintype "passive"))
    )
    (net (code "62") (name "Net-(IC1-CP1)") (class "Default")
      (node (ref "C2") (pin "1") (pinfunction "1_1") (pintype "passive"))
      (node (ref "IC1") (pin "1") (pinfunction "CP1_1") (pintype "bidirectional"))
    )
    (net (code "63") (name "Net-(IC1-CP2)") (class "Default")
      (node (ref "C2") (pin "2") (pinfunction "2_2") (pintype "passive"))
      (node (ref "IC1") (pin "2") (pinfunction "CP2_2") (pintype "bidirectional"))
    )
    (net (code "64") (name "Net-(IC1-OUT1)") (class "Default")
      (node (ref "IC1") (pin "5") (pinfunction "OUT1_5") (pintype "output"))
      (node (ref "P3") (pin "6") (pinfunction "6_6") (pintype "passive"))
    )
    (net (code "65") (name "Net-(IC1-OUT2)") (class "Default")
      (node (ref "IC1") (pin "7") (pinfunction "OUT2_7") (pintype "output"))
      (node (ref "P3") (pin "1") (pinfunction "1_1") (pintype "passive"))
    )
    (net (code "66") (name "Net-(IC1-OUT3)") (class "Default")
      (node (ref "IC1") (pin "8") (pinfunction "OUT3_8") (pintype "output"))
      (node (ref "P1") (pin "6") (pinfunction "6_6") (pintype "passive"))
    )
    (net (code "67") (name "Net-(IC1-OUT4)") (class "Default")
      (node (ref "IC1") (pin "10") (pinfunction "OUT4_10") (pintype "output"))
      (node (ref "P1") (pin "1") (pinfunction "1_1") (pintype "passive"))
    )
    (net (code "68") (name "Net-(IC1-V3P3OUT)") (class "Default")
      (node (ref "C4") (pin "1") (pinfunction "1_1") (pintype "passive"))
      (node (ref "IC1") (pin "15") (pinfunction "V3P3OUT_15") (pintype "output"))
    )
    (net (code "69") (name "Net-(IC1-VCP)") (class "Default")
      (node (ref "C3") (pin "1") (pinfunction "1_1") (pintype "passive"))
      (node (ref "IC1") (pin "3") (pinfunction "VCP_3") (pintype "bidirectional"))
    )
    (net (code "70") (name "Net-(IC2-CP1)") (class "Default")
      (node (ref "C21") (pin "1") (pinfunction "1_1") (pintype "passive"))
      (node (ref "IC2") (pin "1") (pinfunction "CP1_1") (pintype "bidirectional"))
    )
    (net (code "71") (name "Net-(IC2-CP2)") (class "Default")
      (node (ref "C21") (pin "2") (pinfunction "2_2") (pintype "passive"))
      (node (ref "IC2") (pin "2") (pinfunction "CP2_2") (pintype "bidirectional"))
    )
    (net (code "72") (name "Net-(IC2-OUT1)") (class "Default")
      (node (ref "IC2") (pin "5") (pinfunction "OUT1_5") (pintype "output"))
      (node (ref "P4") (pin "6") (pinfunction "6_6") (pintype "passive"))
    )
    (net (code "73") (name "Net-(IC2-OUT2)") (class "Default")
      (node (ref "IC2") (pin "7") (pinfunction "OUT2_7") (pintype "output"))
      (node (ref "P4") (pin "1") (pinfunction "1_1") (pintype "passive"))
    )
    (net (code "74") (name "Net-(IC2-OUT3)") (class "Default")
      (node (ref "IC2") (pin "8") (pinfunction "OUT3_8") (pintype "output"))
      (node (ref "P2") (pin "6") (pinfunction "6_6") (pintype "passive"))
    )
    (net (code "75") (name "Net-(IC2-OUT4)") (class "Default")
      (node (ref "IC2") (pin "10") (pinfunction "OUT4_10") (pintype "output"))
      (node (ref "P2") (pin "1") (pinfunction "1_1") (pintype "passive"))
    )
    (net (code "76") (name "Net-(IC2-V3P3OUT)") (class "Default")
      (node (ref "C25") (pin "1") (pinfunction "1_1") (pintype "passive"))
      (node (ref "IC2") (pin "15") (pinfunction "V3P3OUT_15") (pintype "output"))
    )
    (net (code "77") (name "Net-(IC2-VCP)") (class "Default")
      (node (ref "C22") (pin "1") (pinfunction "1_1") (pintype "passive"))
      (node (ref "IC2") (pin "3") (pinfunction "VCP_3") (pintype "bidirectional"))
    )
    (net (code "78") (name "Net-(J1-Pad2)") (class "Default")
      (node (ref "J1") (pin "2") (pinfunction "2_2") (pintype "passive"))
      (node (ref "R14") (pin "2") (pinfunction "2_2") (pintype "passive"))
    )
    (net (code "79") (name "Net-(J1-Pad3)") (class "Default")
      (node (ref "J1") (pin "3") (pinfunction "3_3") (pintype "passive"))
      (node (ref "R12") (pin "1") (pinfunction "1_1") (pintype "passive"))
      (node (ref "R18") (pin "2") (pinfunction "2_2") (pintype "passive"))
    )
    (net (code "80") (name "Net-(J1-Pad4)") (class "Default")
      (node (ref "J1") (pin "4") (pinfunction "4_4") (pintype "passive"))
      (node (ref "R16") (pin "2") (pinfunction "2_2") (pintype "passive"))
    )
    (net (code "81") (name "Net-(J1-SHIELD-PadSH1)") (class "Default")
      (node (ref "J1") (pin "SH1") (pinfunction "SHIELD_SH1") (pintype "passive"))
      (node (ref "J1") (pin "SH2") (pinfunction "SHIELD_SH2") (pintype "passive"))
      (node (ref "J1") (pin "SH3") (pinfunction "SHIELD_SH3") (pintype "passive"))
      (node (ref "J1") (pin "SH4") (pinfunction "SHIELD_SH4") (pintype "passive"))
      (node (ref "J1") (pin "SH5") (pinfunction "SHIELD_SH5") (pintype "passive"))
      (node (ref "R19") (pin "2") (pinfunction "2_2") (pintype "passive"))
    )
    (net (code "82") (name "Net-(LED1-A)") (class "Default")
      (node (ref "LED1") (pin "2") (pinfunction "A_2") (pintype "bidirectional"))
      (node (ref "R5") (pin "1") (pinfunction "1_1") (pintype "passive"))
    )
    (net (code "83") (name "Net-(LIDAR_MOTOR-1)") (class "Default")
      (node (ref "D1") (pin "A") (pinfunction "A_A") (pintype "passive"))
      (node (ref "LIDAR_MOTOR") (pin "P1") (pinfunction "1_P1") (pintype "bidirectional"))
      (node (ref "M1") (pin "3") (pinfunction "D_3") (pintype "passive"))
    )
    (net (code "84") (name "Net-(M1-G)") (class "Default")
      (node (ref "M1") (pin "1") (pinfunction "G_1") (pintype "passive"))
      (node (ref "R38") (pin "2") (pinfunction "2_2") (pintype "passive"))
      (node (ref "R9") (pin "2") (pinfunction "2_2") (pintype "passive"))
    )
    (net (code "85") (name "Net-(M2-G)") (class "Default")
      (node (ref "M2") (pin "1") (pinfunction "G_1") (pintype "passive"))
      (node (ref "R13") (pin "2") (pinfunction "2_2") (pintype "passive"))
      (node (ref "R22") (pin "2") (pinfunction "2_2") (pintype "passive"))
    )
    (net (code "86") (name "Net-(M3-G)") (class "Default")
      (node (ref "M3") (pin "1") (pinfunction "G_1") (pintype "passive"))
      (node (ref "R11") (pin "2") (pinfunction "2_2") (pintype "passive"))
      (node (ref "R6") (pin "2") (pinfunction "2_2") (pintype "passive"))
    )
    (net (code "87") (name "Net-(P1-Pad2)") (class "Default")
      (node (ref "P1") (pin "2") (pinfunction "2_2") (pintype "passive"))
      (node (ref "P3") (pin "2") (pinfunction "2_2") (pintype "passive"))
      (node (ref "SJ3") (pin "2") (pinfunction "2_2") (pintype "passive"))
    )
    (net (code "88") (name "Net-(P2-Pad2)") (class "Default")
      (node (ref "P2") (pin "2") (pinfunction "2_2") (pintype "passive"))
      (node (ref "P4") (pin "2") (pinfunction "2_2") (pintype "passive"))
      (node (ref "SJ1") (pin "2") (pinfunction "2_2") (pintype "passive"))
    )
    (net (code "89") (name "Net-(PCA9533-LED0)") (class "Default")
      (node (ref "PCA9533") (pin "1") (pinfunction "LED0_1") (pintype "bidirectional"))
      (node (ref "R26") (pin "1") (pinfunction "1_1") (pintype "passive"))
    )
    (net (code "90") (name "Net-(PCA9533-LED1)") (class "Default")
      (node (ref "PCA9533") (pin "2") (pinfunction "LED1_2") (pintype "bidirectional"))
      (node (ref "R27") (pin "1") (pinfunction "1_1") (pintype "passive"))
    )
    (net (code "91") (name "Net-(PCA9533-LED2)") (class "Default")
      (node (ref "PCA9533") (pin "3") (pinfunction "LED2_3") (pintype "bidirectional"))
      (node (ref "R28") (pin "1") (pinfunction "1_1") (pintype "passive"))
    )
    (net (code "92") (name "Net-(R19-Pad1)") (class "Default")
      (node (ref "R19") (pin "1") (pinfunction "1_1") (pintype "passive"))
      (node (ref "SJ2") (pin "2") (pinfunction "2_2") (pintype "passive"))
    )
    (net (code "93") (name "Net-(RGB_LED-2)") (class "Default")
      (node (ref "R28") (pin "2") (pinfunction "2_2") (pintype "passive"))
      (node (ref "RGB_LED") (pin "P2") (pinfunction "2_P2") (pintype "bidirectional"))
    )
    (net (code "94") (name "Net-(RGB_LED-3)") (class "Default")
      (node (ref "R27") (pin "2") (pinfunction "2_2") (pintype "passive"))
      (node (ref "RGB_LED") (pin "P3") (pinfunction "3_P3") (pintype "bidirectional"))
    )
    (net (code "95") (name "Net-(RGB_LED-4)") (class "Default")
      (node (ref "R26") (pin "2") (pinfunction "2_2") (pintype "passive"))
      (node (ref "RGB_LED") (pin "P4") (pinfunction "4_P4") (pintype "bidirectional"))
    )
    (net (code "96") (name "Net-(U1-BOOT0)") (class "Default")
      (node (ref "R7") (pin "1") (pinfunction "1_1") (pintype "passive"))
      (node (ref "U1") (pin "94") (pinfunction "BOOT0_94") (pintype "input"))
    )
    (net (code "97") (name "Net-(U1-PH1)") (class "Default")
      (node (ref "ABM8G-25.000MHZ-18-D2Y-T3") (pin "1") (pinfunction "1_1") (pintype "passive"))
      (node (ref "C11") (pin "2") (pinfunction "2_2") (pintype "passive"))
      (node (ref "U1") (pin "13") (pinfunction "PH1_13") (pintype "bidirectional"))
    )
    (net (code "98") (name "Net-(U1-VCAP_1)") (class "Default")
      (node (ref "C29") (pin "2") (pinfunction "2_2") (pintype "passive"))
      (node (ref "U1") (pin "49") (pinfunction "VCAP_1_49") (pintype "power_in"))
    )
    (net (code "99") (name "Net-(U1-VCAP_2)") (class "Default")
      (node (ref "C32") (pin "2") (pinfunction "2_2") (pintype "passive"))
      (node (ref "U1") (pin "73") (pinfunction "VCAP_2_73") (pintype "power_in"))
    )
    (net (code "100") (name "Net-(U3-REGOUT)") (class "Default")
      (node (ref "C7") (pin "1") (pinfunction "1_1") (pintype "passive"))
      (node (ref "U3") (pin "10") (pinfunction "REGOUT_10") (pintype "output"))
    )
    (net (code "101") (name "V+") (class "Default")
      (node (ref "C16") (pin "1") (pinfunction "1_1") (pintype "passive"))
      (node (ref "C27") (pin "+") (pinfunction "+_+") (pintype "passive"))
      (node (ref "INA219") (pin "1") (pinfunction "VIN+_1") (pintype "bidirectional"))
      (node (ref "PWR") (pin "1") (pinfunction "1_1") (pintype "passive"))
      (node (ref "R17") (pin "2") (pinfunction "2_2") (pintype "passive"))
      (node (ref "R34") (pin "2") (pinfunction "2_2") (pintype "passive"))
    )
    (net (code "102") (name "unconnected-(IC1-NC_1-Pad12)") (class "Default")
      (node (ref "IC1") (pin "12") (pinfunction "NC_1_12") (pintype "bidirectional"))
    )
    (net (code "103") (name "unconnected-(IC1-NC_2-Pad13)") (class "Default")
      (node (ref "IC1") (pin "13") (pinfunction "NC_2_13") (pintype "bidirectional"))
    )
    (net (code "104") (name "unconnected-(IC2-NC_1-Pad12)") (class "Default")
      (node (ref "IC2") (pin "12") (pinfunction "NC_1_12") (pintype "bidirectional"))
    )
    (net (code "105") (name "unconnected-(IC2-NC_2-Pad13)") (class "Default")
      (node (ref "IC2") (pin "13") (pinfunction "NC_2_13") (pintype "bidirectional"))
    )
    (net (code "106") (name "unconnected-(PCA9533-LED3-Pad5)") (class "Default")
      (node (ref "PCA9533") (pin "5") (pinfunction "LED3_5") (pintype "bidirectional"))
    )
    (net (code "107") (name "unconnected-(RPI_ZERO-Pad2)") (class "Default")
      (node (ref "RPI_ZERO") (pin "2") (pinfunction "2_2") (pintype "passive"))
    )
    (net (code "108") (name "unconnected-(RPI_ZERO-Pad3)") (class "Default")
      (node (ref "RPI_ZERO") (pin "3") (pinfunction "3_3") (pintype "passive"))
    )
    (net (code "109") (name "unconnected-(RPI_ZERO-Pad4)") (class "Default")
      (node (ref "RPI_ZERO") (pin "4") (pinfunction "4_4") (pintype "passive"))
    )
    (net (code "110") (name "unconnected-(RPI_ZERO-Pad5)") (class "Default")
      (node (ref "RPI_ZERO") (pin "5") (pinfunction "5_5") (pintype "passive"))
    )
    (net (code "111") (name "unconnected-(RPI_ZERO-Pad6)") (class "Default")
      (node (ref "RPI_ZERO") (pin "6") (pinfunction "6_6") (pintype "passive"))
    )
    (net (code "112") (name "unconnected-(RPI_ZERO-Pad7)") (class "Default")
      (node (ref "RPI_ZERO") (pin "7") (pinfunction "7_7") (pintype "passive"))
    )
    (net (code "113") (name "unconnected-(RPI_ZERO-Pad9)") (class "Default")
      (node (ref "RPI_ZERO") (pin "9") (pinfunction "9_9") (pintype "passive"))
    )
    (net (code "114") (name "unconnected-(RPI_ZERO-Pad10)") (class "Default")
      (node (ref "RPI_ZERO") (pin "10") (pinfunction "10_10") (pintype "passive"))
    )
    (net (code "115") (name "unconnected-(RPI_ZERO-Pad11)") (class "Default")
      (node (ref "RPI_ZERO") (pin "11") (pinfunction "11_11") (pintype "passive"))
    )
    (net (code "116") (name "unconnected-(RPI_ZERO-Pad13)") (class "Default")
      (node (ref "RPI_ZERO") (pin "13") (pinfunction "13_13") (pintype "passive"))
    )
    (net (code "117") (name "unconnected-(RPI_ZERO-Pad14)") (class "Default")
      (node (ref "RPI_ZERO") (pin "14") (pinfunction "14_14") (pintype "passive"))
    )
    (net (code "118") (name "unconnected-(RPI_ZERO-Pad16)") (class "Default")
      (node (ref "RPI_ZERO") (pin "16") (pinfunction "16_16") (pintype "passive"))
    )
    (net (code "119") (name "unconnected-(RPI_ZERO-Pad17)") (class "Default")
      (node (ref "RPI_ZERO") (pin "17") (pinfunction "17_17") (pintype "passive"))
    )
    (net (code "120") (name "unconnected-(RPI_ZERO-Pad18)") (class "Default")
      (node (ref "RPI_ZERO") (pin "18") (pinfunction "18_18") (pintype "passive"))
    )
    (net (code "121") (name "unconnected-(RPI_ZERO-Pad19)") (class "Default")
      (node (ref "RPI_ZERO") (pin "19") (pinfunction "19_19") (pintype "passive"))
    )
    (net (code "122") (name "unconnected-(RPI_ZERO-Pad21)") (class "Default")
      (node (ref "RPI_ZERO") (pin "21") (pinfunction "21_21") (pintype "passive"))
    )
    (net (code "123") (name "unconnected-(RPI_ZERO-Pad23)") (class "Default")
      (node (ref "RPI_ZERO") (pin "23") (pinfunction "23_23") (pintype "passive"))
    )
    (net (code "124") (name "unconnected-(RPI_ZERO-Pad25)") (class "Default")
      (node (ref "RPI_ZERO") (pin "25") (pinfunction "25_25") (pintype "passive"))
    )
    (net (code "125") (name "unconnected-(RPI_ZERO-Pad27)") (class "Default")
      (node (ref "RPI_ZERO") (pin "27") (pinfunction "27_27") (pintype "passive"))
    )
    (net (code "126") (name "unconnected-(RPI_ZERO-Pad29)") (class "Default")
      (node (ref "RPI_ZERO") (pin "29") (pinfunction "29_29") (pintype "passive"))
    )
    (net (code "127") (name "unconnected-(RPI_ZERO-Pad30)") (class "Default")
      (node (ref "RPI_ZERO") (pin "30") (pinfunction "30_30") (pintype "passive"))
    )
    (net (code "128") (name "unconnected-(RPI_ZERO-Pad33)") (class "Default")
      (node (ref "RPI_ZERO") (pin "33") (pinfunction "33_33") (pintype "passive"))
    )
    (net (code "129") (name "unconnected-(RPI_ZERO-Pad35)") (class "Default")
      (node (ref "RPI_ZERO") (pin "35") (pinfunction "35_35") (pintype "passive"))
    )
    (net (code "130") (name "unconnected-(RPI_ZERO-Pad37)") (class "Default")
      (node (ref "RPI_ZERO") (pin "37") (pinfunction "37_37") (pintype "passive"))
    )
    (net (code "131") (name "unconnected-(RPI_ZERO-Pad39)") (class "Default")
      (node (ref "RPI_ZERO") (pin "39") (pinfunction "39_39") (pintype "passive"))
    )
    (net (code "132") (name "unconnected-(U1-PA4-Pad29)") (class "Default")
      (node (ref "U1") (pin "29") (pinfunction "PA4_29") (pintype "bidirectional"))
    )
    (net (code "133") (name "unconnected-(U1-PA5-Pad30)") (class "Default")
      (node (ref "U1") (pin "30") (pinfunction "PA5_30") (pintype "bidirectional"))
    )
    (net (code "134") (name "unconnected-(U1-PA15-Pad77)") (class "Default")
      (node (ref "U1") (pin "77") (pinfunction "PA15_77") (pintype "bidirectional"))
    )
    (net (code "135") (name "unconnected-(U1-PB2-Pad37)") (class "Default")
      (node (ref "U1") (pin "37") (pinfunction "PB2_37") (pintype "bidirectional"))
    )
    (net (code "136") (name "unconnected-(U1-PB12-Pad51)") (class "Default")
      (node (ref "U1") (pin "51") (pinfunction "PB12_51") (pintype "bidirectional"))
    )
    (net (code "137") (name "unconnected-(U1-PB13-Pad52)") (class "Default")
      (node (ref "U1") (pin "52") (pinfunction "PB13_52") (pintype "bidirectional"))
    )
    (net (code "138") (name "unconnected-(U1-PB14-Pad53)") (class "Default")
      (node (ref "U1") (pin "53") (pinfunction "PB14_53") (pintype "bidirectional"))
    )
    (net (code "139") (name "unconnected-(U1-PB15-Pad54)") (class "Default")
      (node (ref "U1") (pin "54") (pinfunction "PB15_54") (pintype "bidirectional"))
    )
    (net (code "140") (name "unconnected-(U1-PC1-Pad16)") (class "Default")
      (node (ref "U1") (pin "16") (pinfunction "PC1_16") (pintype "bidirectional"))
    )
    (net (code "141") (name "unconnected-(U1-PC2-Pad17)") (class "Default")
      (node (ref "U1") (pin "17") (pinfunction "PC2_17") (pintype "bidirectional"))
    )
    (net (code "142") (name "unconnected-(U1-PC3-Pad18)") (class "Default")
      (node (ref "U1") (pin "18") (pinfunction "PC3_18") (pintype "bidirectional"))
    )
    (net (code "143") (name "unconnected-(U1-PC4-Pad33)") (class "Default")
      (node (ref "U1") (pin "33") (pinfunction "PC4_33") (pintype "bidirectional"))
    )
    (net (code "144") (name "unconnected-(U1-PC5-Pad34)") (class "Default")
      (node (ref "U1") (pin "34") (pinfunction "PC5_34") (pintype "bidirectional"))
    )
    (net (code "145") (name "unconnected-(U1-PC8-Pad65)") (class "Default")
      (node (ref "U1") (pin "65") (pinfunction "PC8_65") (pintype "bidirectional"))
    )
    (net (code "146") (name "unconnected-(U1-PC13-Pad7)") (class "Default")
      (node (ref "U1") (pin "7") (pinfunction "PC13_7") (pintype "bidirectional"))
    )
    (net (code "147") (name "unconnected-(U1-PC14-Pad8)") (class "Default")
      (node (ref "U1") (pin "8") (pinfunction "PC14_8") (pintype "bidirectional"))
    )
    (net (code "148") (name "unconnected-(U1-PC15-Pad9)") (class "Default")
      (node (ref "U1") (pin "9") (pinfunction "PC15_9") (pintype "bidirectional"))
    )
    (net (code "149") (name "unconnected-(U1-PD10-Pad57)") (class "Default")
      (node (ref "U1") (pin "57") (pinfunction "PD10_57") (pintype "bidirectional"))
    )
    (net (code "150") (name "unconnected-(U1-PD11-Pad58)") (class "Default")
      (node (ref "U1") (pin "58") (pinfunction "PD11_58") (pintype "bidirectional"))
    )
    (net (code "151") (name "unconnected-(U1-PD14-Pad61)") (class "Default")
      (node (ref "U1") (pin "61") (pinfunction "PD14_61") (pintype "bidirectional"))
    )
    (net (code "152") (name "unconnected-(U1-PD15-Pad62)") (class "Default")
      (node (ref "U1") (pin "62") (pinfunction "PD15_62") (pintype "bidirectional"))
    )
    (net (code "153") (name "unconnected-(U1-PE0-Pad97)") (class "Default")
      (node (ref "U1") (pin "97") (pinfunction "PE0_97") (pintype "bidirectional"))
    )
    (net (code "154") (name "unconnected-(U1-PE1-Pad98)") (class "Default")
      (node (ref "U1") (pin "98") (pinfunction "PE1_98") (pintype "bidirectional"))
    )
    (net (code "155") (name "unconnected-(U1-PE2-Pad1)") (class "Default")
      (node (ref "U1") (pin "1") (pinfunction "PE2_1") (pintype "bidirectional"))
    )
    (net (code "156") (name "unconnected-(U1-PE3-Pad2)") (class "Default")
      (node (ref "U1") (pin "2") (pinfunction "PE3_2") (pintype "bidirectional"))
    )
    (net (code "157") (name "unconnected-(U1-PE4-Pad3)") (class "Default")
      (node (ref "U1") (pin "3") (pinfunction "PE4_3") (pintype "bidirectional"))
    )
    (net (code "158") (name "unconnected-(U1-PE7-Pad38)") (class "Default")
      (node (ref "U1") (pin "38") (pinfunction "PE7_38") (pintype "bidirectional"))
    )
    (net (code "159") (name "unconnected-(U1-PE8-Pad39)") (class "Default")
      (node (ref "U1") (pin "39") (pinfunction "PE8_39") (pintype "bidirectional"))
    )
    (net (code "160") (name "unconnected-(U1-PE10-Pad41)") (class "Default")
      (node (ref "U1") (pin "41") (pinfunction "PE10_41") (pintype "bidirectional"))
    )
    (net (code "161") (name "unconnected-(U1-PE12-Pad43)") (class "Default")
      (node (ref "U1") (pin "43") (pinfunction "PE12_43") (pintype "bidirectional"))
    )
    (net (code "162") (name "unconnected-(U1-PE15-Pad46)") (class "Default")
      (node (ref "U1") (pin "46") (pinfunction "PE15_46") (pintype "bidirectional"))
    )
    (net (code "163") (name "unconnected-(U3-AD0{slash}SDO-Pad9)") (class "Default")
      (node (ref "U3") (pin "9") (pinfunction "AD0/SDO_9") (pintype "output"))
    )
    (net (code "164") (name "unconnected-(U3-AUX_CL-Pad7)") (class "Default")
      (node (ref "U3") (pin "7") (pinfunction "AUX_CL_7") (pintype "input"))
    )
    (net (code "165") (name "unconnected-(U3-AUX_DA-Pad21)") (class "Default")
      (node (ref "U3") (pin "21") (pinfunction "AUX_DA_21") (pintype "input"))
    )
    (net (code "166") (name "unconnected-(U3-FSYNC-Pad11)") (class "Default")
      (node (ref "U3") (pin "11") (pinfunction "FSYNC_11") (pintype "input"))
    )
    (net (code "167") (name "unconnected-(U3-INT1-Pad12)") (class "Default")
      (node (ref "U3") (pin "12") (pinfunction "INT1_12") (pintype "output"))
    )
    (net (code "168") (name "unconnected-(U3-NCS-Pad22)") (class "Default")
      (node (ref "U3") (pin "22") (pinfunction "NCS_22") (pintype "input"))
    )
    (net (code "169") (name "unconnected-(U3-RESV_19-Pad19)") (class "Default")
      (node (ref "U3") (pin "19") (pinfunction "RESV_19_19") (pintype "passive"))
    )
    (net (code "170") (name "unconnected-(U3-RESV_20-Pad20)") (class "Default")
      (node (ref "U3") (pin "20") (pinfunction "RESV_20_20") (pintype "passive"))
    )
  )
)
